# EntradasAnalogicas.net
KiCad netlist of a schematic drawn in Altium Designer
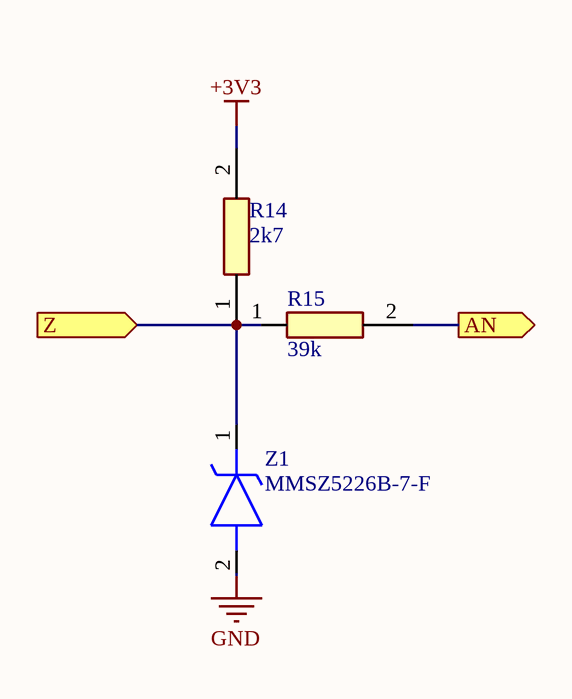
[diagram p0: EntradasAnalogicas.SchDoc]

(export (version "E")
  (design (tool "Eeschema 10.0.6"))
  (components
    (comp (ref "R14")
      (value "2k7")
      (footprint "SamacSys:RESC3216X75N")
      (description "Resistor")
      (fields
        (field (name "MANUFACTURER_PART_NUMBER") "CR1206-F/-2R00ELF")
        (field (name "MOUSER PART NUMBER") "652-CR1206-F/2R00ELF")
      )
      (libsource (lib "") (part "CR1206-F_-2R00ELF_1"))
    )
    (comp (ref "R15")
      (value "39k")
      (footprint "SamacSys:RESC3216X75N")
      (description "Resistor")
      (fields
        (field (name "MANUFACTURER_PART_NUMBER") "CR1206-F/-2R00ELF")
        (field (name "MOUSER PART NUMBER") "652-CR1206-F/2R00ELF")
      )
      (libsource (lib "*") (part "CR1206-F_-2R00ELF"))
    )
    (comp (ref "Z1")
      (value "MMSZ5226B-7-F")
      (footprint "SamacSys:MMSZ5226B7F")
      (description "Zener Diode")
      (fields (field (name "MOUSER PART NUMBER") "621-MMSZ5226B-F"))
      (libsource (lib "*") (part "MMSZ5226B-7-F"))
    )
  )
  (nets
    (net (code "1") (name "+3V3") (class "Default")
      (node (ref "R14") (pin "2") (pinfunction "2_2") (pintype "passive"))
    )
    (net (code "2") (name "/AN") (class "Default")
      (node (ref "R15") (pin "2") (pinfunction "2_2") (pintype "passive"))
    )
    (net (code "3") (name "/Z") (class "Default")
      (node (ref "R14") (pin "1") (pinfunction "1_1") (pintype "passive"))
      (node (ref "R15") (pin "1") (pinfunction "1_1") (pintype "passive"))
      (node (ref "Z1") (pin "1") (pinfunction "K_1") (pintype "passive"))
    )
    (net (code "4") (name "GND") (class "Default")
      (node (ref "Z1") (pin "2") (pinfunction "A_2") (pintype "passive"))
    )
  )
)
